# 1_MCU.net
KiCad netlist of a schematic drawn in Altium Designer
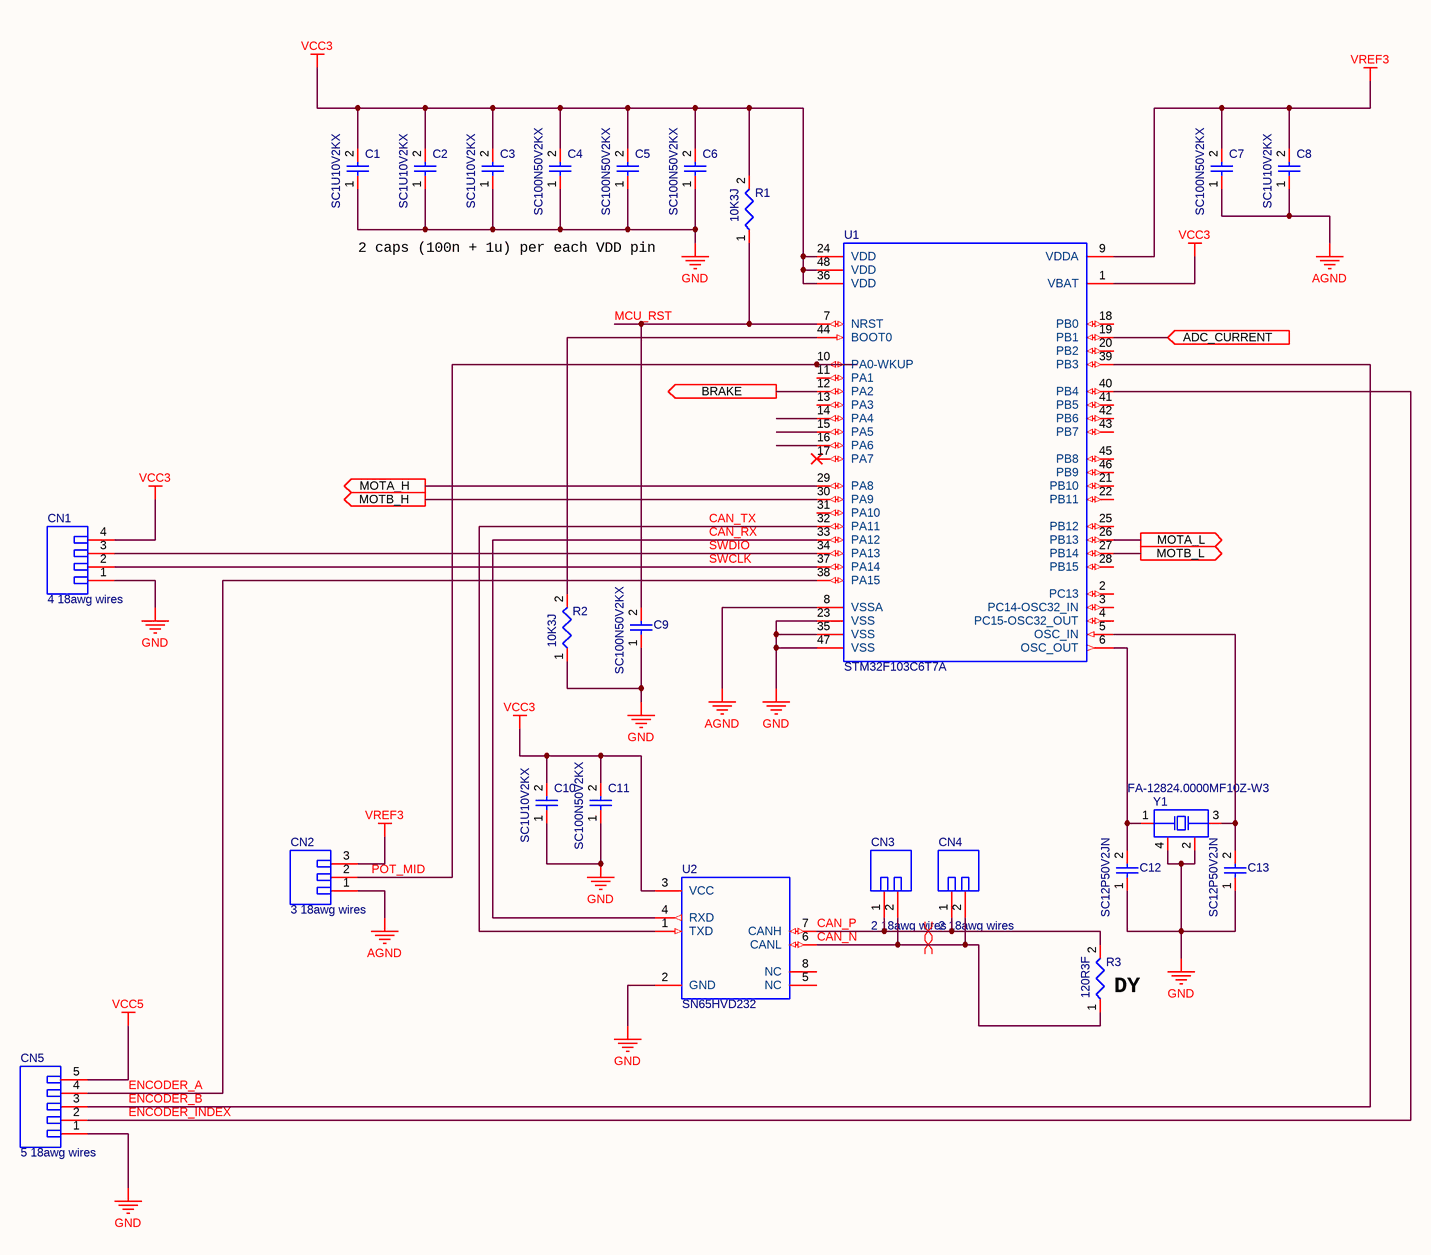
[diagram p0: 1_MCU.SchDoc]

(export (version "E")
  (design (tool "Eeschema 10.0.6"))
  (components
    (comp (ref "C1")
      (value "SC1U10V2KX")
      (footprint "CAPC0402(1005)60_L")
      (description "CAP 1uF 10V ±10% 0402 (1005 Metric) Thickness 0.6mm SMD")
      (libsource (lib "Schlib") (part "CAP(0402)1UF10V"))
    )
    (comp (ref "C2")
      (value "SC1U10V2KX")
      (footprint "CAPC0402(1005)60_L")
      (description "CAP 1uF 10V ±10% 0402 (1005 Metric) Thickness 0.6mm SMD")
      (libsource (lib "Schlib") (part "CAP(0402)1UF10V"))
    )
    (comp (ref "C3")
      (value "SC1U10V2KX")
      (footprint "CAPC0402(1005)60_L")
      (description "CAP 1uF 10V ±10% 0402 (1005 Metric) Thickness 0.6mm SMD")
      (libsource (lib "Schlib") (part "CAP(0402)1UF10V"))
    )
    (comp (ref "C4")
      (value "SC100N50V2KX")
      (footprint "CAPC0402(1005)60_L")
      (description "CAP 100nF 50V ±10% 0402 (1005 Metric) Thickness 0.6mm SMD")
      (libsource (lib "Schlib") (part "CAP(0402)100nF50V"))
    )
    (comp (ref "C5")
      (value "SC100N50V2KX")
      (footprint "CAPC0402(1005)60_L")
      (description "CAP 100nF 50V ±10% 0402 (1005 Metric) Thickness 0.6mm SMD")
      (libsource (lib "Schlib") (part "CAP(0402)100nF50V"))
    )
    (comp (ref "C6")
      (value "SC100N50V2KX")
      (footprint "CAPC0402(1005)60_L")
      (description "CAP 100nF 50V ±10% 0402 (1005 Metric) Thickness 0.6mm SMD")
      (libsource (lib "Schlib") (part "CAP(0402)100nF50V"))
    )
    (comp (ref "C7")
      (value "SC100N50V2KX")
      (footprint "CAPC0402(1005)60_L")
      (description "CAP 100nF 50V ±10% 0402 (1005 Metric) Thickness 0.6mm SMD")
      (libsource (lib "Schlib") (part "CAP(0402)100nF50V"))
    )
    (comp (ref "C8")
      (value "SC1U10V2KX")
      (footprint "CAPC0402(1005)60_L")
      (description "CAP 1uF 10V ±10% 0402 (1005 Metric) Thickness 0.6mm SMD")
      (libsource (lib "Schlib") (part "CAP(0402)1UF10V"))
    )
    (comp (ref "C9")
      (value "SC100N50V2KX")
      (footprint "CAPC0402(1005)60_L")
      (description "CAP 100nF 50V ±10% 0402 (1005 Metric) Thickness 0.6mm SMD")
      (libsource (lib "Schlib") (part "CAP(0402)100nF50V"))
    )
    (comp (ref "C10")
      (value "SC1U10V2KX")
      (footprint "CAPC0402(1005)60_L")
      (description "CAP 1uF 10V ±10% 0402 (1005 Metric) Thickness 0.6mm SMD")
      (libsource (lib "Schlib") (part "CAP(0402)1UF10V"))
    )
    (comp (ref "C11")
      (value "SC100N50V2KX")
      (footprint "CAPC0402(1005)60_L")
      (description "CAP 100nF 50V ±10% 0402 (1005 Metric) Thickness 0.6mm SMD")
      (libsource (lib "Schlib") (part "CAP(0402)100nF50V"))
    )
    (comp (ref "C12")
      (value "SC12P50V2JN")
      (footprint "CAPC0402(1005)33_L")
      (description "CAP 12pF 50V ±5% 0402 (1005 Metric) Thickness 0.33mm SMD")
      (libsource (lib "PUMAlib") (part "CAP12pF"))
    )
    (comp (ref "C13")
      (value "SC12P50V2JN")
      (footprint "CAPC0402(1005)33_L")
      (description "CAP 12pF 50V ±5% 0402 (1005 Metric) Thickness 0.33mm SMD")
      (libsource (lib "PUMAlib") (part "CAP12pF"))
    )
    (comp (ref "CN1")
      (value "4 18awg wires")
      (footprint "4PHEADERS-2D54")
      (description "4 holes for 18awg wire")
      (fields (field (name "MANUFACTURER") "JST"))
      (libsource (lib "PUMAlib") (part "4PIN-CN"))
    )
    (comp (ref "CN2")
      (value "3 18awg wires")
      (footprint "3PHEADERS-2D54")
      (description "3 holes for 18awg wire")
      (fields (field (name "MANUFACTURER") "JST"))
      (libsource (lib "PUMAlib") (part "3PIN-CN"))
    )
    (comp (ref "CN3")
      (value "2 18awg wires")
      (footprint "2PHEADERS-2D54")
      (description "2 holes for 18awg wire")
      (fields (field (name "MANUFACTURER") "JST"))
      (libsource (lib "PDB") (part "2PIN-CN"))
    )
    (comp (ref "CN4")
      (value "2 18awg wires")
      (footprint "2PHEADERS-2D54")
      (description "2 holes for 18awg wire")
      (fields (field (name "MANUFACTURER") "JST"))
      (libsource (lib "PDB") (part "2PIN-CN"))
    )
    (comp (ref "CN5")
      (value "5 18awg wires")
      (footprint "5PHEADERS-2D54")
      (description "5 holes for 18awg wire")
      (fields (field (name "MANUFACTURER") "JST"))
      (libsource (lib "PUMAlib") (part "5PIN-CN"))
    )
    (comp (ref "R1")
      (value "10K3J")
      (footprint "RESC0603(1608)_L")
      (description "10K 0.1W 5% 0603 (1608 Metric)  SMD")
      (libsource (lib "Schlib") (part "RES0(0603)_10K"))
    )
    (comp (ref "R2")
      (value "10K3J")
      (footprint "RESC0603(1608)_L")
      (description "10K 0.1W 5% 0603 (1608 Metric)  SMD")
      (libsource (lib "Schlib") (part "RES0(0603)_10K"))
    )
    (comp (ref "R3")
      (value "120R3F")
      (footprint "RESC0603(1608)_L")
      (description "100R 0.1W 1% 0603 (1608 Metric)  SMD")
      (libsource (lib "PUMAlib") (part "RES0(0603)_120R"))
    )
    (comp (ref "U1")
      (value "STM32F103C6T7A")
      (footprint "TSQFP50P900X900X160-48L")
      (description "ARM® Cortex®-M3 STM32F1 Microcontroller IC 32-Bit 72MHz 32KB 48-LFQP (7x7)")
      (libsource (lib "PUMAlib") (part "STM32F103C6T7A"))
    )
    (comp (ref "U2")
      (value "SN65HVD232")
      (footprint "SOIC127P600X175-8L")
      (description "IC CAN TRANSCEIVER 8-SOIC")
      (libsource (lib "PUMAlib") (part "CAN_SN65HVD232D"))
    )
    (comp (ref "Y1")
      (value "FA-12824.0000MF10Z-W3")
      (footprint "QRTZ-12mhz")
      (description "Crystal, 24 MHz, +/- 10 ppm, -20 to 75 degC, 4-Pin SMD, RoHS, Tape and Reel")
      (fields (field (name "TOLERANCE") "10ppm"))
      (libsource (lib "PUMAlib") (part "XTAL-1-3-4"))
    )
  )
  (nets
    (net (code "1") (name "/ADC_CURRENT") (class "Default")
      (node (ref "U1") (pin "19") (pinfunction "PB1_19") (pintype "bidirectional"))
    )
    (net (code "2") (name "/BRAKE") (class "Default")
      (node (ref "U1") (pin "12") (pinfunction "PA2_12") (pintype "bidirectional"))
    )
    (net (code "3") (name "/CAN_N") (class "Default")
      (node (ref "CN3") (pin "2") (pinfunction "2_2") (pintype "passive"))
      (node (ref "CN4") (pin "2") (pinfunction "2_2") (pintype "passive"))
      (node (ref "R3") (pin "1") (pinfunction "1_1") (pintype "passive"))
      (node (ref "U2") (pin "6") (pinfunction "CANL_6") (pintype "bidirectional"))
    )
    (net (code "4") (name "/CAN_P") (class "Default")
      (node (ref "CN3") (pin "1") (pinfunction "1_1") (pintype "passive"))
      (node (ref "CN4") (pin "1") (pinfunction "1_1") (pintype "passive"))
      (node (ref "R3") (pin "2") (pinfunction "2_2") (pintype "passive"))
      (node (ref "U2") (pin "7") (pinfunction "CANH_7") (pintype "bidirectional"))
    )
    (net (code "5") (name "/CAN_RX") (class "Default")
      (node (ref "U1") (pin "33") (pinfunction "PA12_33") (pintype "bidirectional"))
      (node (ref "U2") (pin "4") (pinfunction "RXD_4") (pintype "output"))
    )
    (net (code "6") (name "/CAN_TX") (class "Default")
      (node (ref "U1") (pin "32") (pinfunction "PA11_32") (pintype "bidirectional"))
      (node (ref "U2") (pin "1") (pinfunction "TXD_1") (pintype "input"))
    )
    (net (code "7") (name "/ENCODER_A") (class "Default")
      (node (ref "CN5") (pin "4") (pinfunction "4_4") (pintype "passive"))
      (node (ref "U1") (pin "38") (pinfunction "PA15_38") (pintype "bidirectional"))
    )
    (net (code "8") (name "/ENCODER_B") (class "Default")
      (node (ref "CN5") (pin "3") (pinfunction "3_3") (pintype "passive"))
      (node (ref "U1") (pin "39") (pinfunction "PB3_39") (pintype "bidirectional"))
    )
    (net (code "9") (name "/ENCODER_INDEX") (class "Default")
      (node (ref "CN5") (pin "2") (pinfunction "2_2") (pintype "passive"))
      (node (ref "U1") (pin "40") (pinfunction "PB4_40") (pintype "bidirectional"))
    )
    (net (code "10") (name "/MCU_RST") (class "Default")
      (node (ref "C9") (pin "2") (pinfunction "2_2") (pintype "passive"))
      (node (ref "R1") (pin "1") (pinfunction "1_1") (pintype "passive"))
      (node (ref "U1") (pin "7") (pinfunction "NRST_7") (pintype "bidirectional"))
    )
    (net (code "11") (name "/MOTA_H") (class "Default")
      (node (ref "U1") (pin "29") (pinfunction "PA8_29") (pintype "bidirectional"))
    )
    (net (code "12") (name "/MOTA_L") (class "Default")
      (node (ref "U1") (pin "26") (pinfunction "PB13_26") (pintype "bidirectional"))
    )
    (net (code "13") (name "/MOTB_H") (class "Default")
      (node (ref "U1") (pin "30") (pinfunction "PA9_30") (pintype "bidirectional"))
    )
    (net (code "14") (name "/MOTB_L") (class "Default")
      (node (ref "U1") (pin "27") (pinfunction "PB14_27") (pintype "bidirectional"))
    )
    (net (code "15") (name "/POT_MID") (class "Default")
      (node (ref "CN2") (pin "2") (pinfunction "2_2") (pintype "passive"))
      (node (ref "U1") (pin "10") (pinfunction "PA0-WKUP_10") (pintype "bidirectional"))
    )
    (net (code "16") (name "/SWCLK") (class "Default")
      (node (ref "CN1") (pin "2") (pinfunction "2_2") (pintype "passive"))
      (node (ref "U1") (pin "37") (pinfunction "PA14_37") (pintype "bidirectional"))
    )
    (net (code "17") (name "/SWDIO") (class "Default")
      (node (ref "CN1") (pin "3") (pinfunction "3_3") (pintype "passive"))
      (node (ref "U1") (pin "34") (pinfunction "PA13_34") (pintype "bidirectional"))
    )
    (net (code "18") (name "AGND") (class "Default")
      (node (ref "C7") (pin "1") (pinfunction "1_1") (pintype "passive"))
      (node (ref "C8") (pin "1") (pinfunction "1_1") (pintype "passive"))
      (node (ref "CN2") (pin "1") (pinfunction "1_1") (pintype "passive"))
      (node (ref "U1") (pin "8") (pinfunction "VSSA_8") (pintype "power_in"))
    )
    (net (code "19") (name "GND") (class "Default")
      (node (ref "C1") (pin "1") (pinfunction "1_1") (pintype "passive"))
      (node (ref "C10") (pin "1") (pinfunction "1_1") (pintype "passive"))
      (node (ref "C11") (pin "1") (pinfunction "1_1") (pintype "passive"))
      (node (ref "C12") (pin "1") (pinfunction "1_1") (pintype "passive"))
      (node (ref "C13") (pin "1") (pinfunction "1_1") (pintype "passive"))
      (node (ref "C2") (pin "1") (pinfunction "1_1") (pintype "passive"))
      (node (ref "C3") (pin "1") (pinfunction "1_1") (pintype "passive"))
      (node (ref "C4") (pin "1") (pinfunction "1_1") (pintype "passive"))
      (node (ref "C5") (pin "1") (pinfunction "1_1") (pintype "passive"))
      (node (ref "C6") (pin "1") (pinfunction "1_1") (pintype "passive"))
      (node (ref "C9") (pin "1") (pinfunction "1_1") (pintype "passive"))
      (node (ref "CN1") (pin "1") (pinfunction "1_1") (pintype "passive"))
      (node (ref "CN5") (pin "1") (pinfunction "1_1") (pintype "passive"))
      (node (ref "R2") (pin "1") (pinfunction "1_1") (pintype "passive"))
      (node (ref "U1") (pin "23") (pinfunction "VSS_23") (pintype "power_in"))
      (node (ref "U1") (pin "35") (pinfunction "VSS_35") (pintype "power_in"))
      (node (ref "U1") (pin "47") (pinfunction "VSS_47") (pintype "power_in"))
      (node (ref "U2") (pin "2") (pinfunction "GND_2") (pintype "power_in"))
      (node (ref "Y1") (pin "2") (pinfunction "NC_2") (pintype "power_in"))
      (node (ref "Y1") (pin "4") (pinfunction "NC_4") (pintype "power_in"))
    )
    (net (code "20") (name "Net-(U1-BOOT0)") (class "Default")
      (node (ref "R2") (pin "2") (pinfunction "2_2") (pintype "passive"))
      (node (ref "U1") (pin "44") (pinfunction "BOOT0_44") (pintype "input"))
    )
    (net (code "21") (name "Net-(U1-OSC_IN)") (class "Default")
      (node (ref "C13") (pin "2") (pinfunction "2_2") (pintype "passive"))
      (node (ref "U1") (pin "5") (pinfunction "OSC_IN_5") (pintype "input"))
      (node (ref "Y1") (pin "3") (pinfunction "X2_3") (pintype "passive"))
    )
    (net (code "22") (name "Net-(U1-OSC_OUT)") (class "Default")
      (node (ref "C12") (pin "2") (pinfunction "2_2") (pintype "passive"))
      (node (ref "U1") (pin "6") (pinfunction "OSC_OUT_6") (pintype "output"))
      (node (ref "Y1") (pin "1") (pinfunction "X1_1") (pintype "passive"))
    )
    (net (code "23") (name "VCC3") (class "Default")
      (node (ref "C1") (pin "2") (pinfunction "2_2") (pintype "passive"))
      (node (ref "C10") (pin "2") (pinfunction "2_2") (pintype "passive"))
      (node (ref "C11") (pin "2") (pinfunction "2_2") (pintype "passive"))
      (node (ref "C2") (pin "2") (pinfunction "2_2") (pintype "passive"))
      (node (ref "C3") (pin "2") (pinfunction "2_2") (pintype "passive"))
      (node (ref "C4") (pin "2") (pinfunction "2_2") (pintype "passive"))
      (node (ref "C5") (pin "2") (pinfunction "2_2") (pintype "passive"))
      (node (ref "C6") (pin "2") (pinfunction "2_2") (pintype "passive"))
      (node (ref "CN1") (pin "4") (pinfunction "4_4") (pintype "passive"))
      (node (ref "R1") (pin "2") (pinfunction "2_2") (pintype "passive"))
      (node (ref "U1") (pin "1") (pinfunction "VBAT_1") (pintype "power_in"))
      (node (ref "U1") (pin "24") (pinfunction "VDD_24") (pintype "power_in"))
      (node (ref "U1") (pin "36") (pinfunction "VDD_36") (pintype "power_in"))
      (node (ref "U1") (pin "48") (pinfunction "VDD_48") (pintype "power_in"))
      (node (ref "U2") (pin "3") (pinfunction "VCC_3") (pintype "power_in"))
    )
    (net (code "24") (name "VCC5") (class "Default")
      (node (ref "CN5") (pin "5") (pinfunction "5_5") (pintype "passive"))
    )
    (net (code "25") (name "VREF3") (class "Default")
      (node (ref "C7") (pin "2") (pinfunction "2_2") (pintype "passive"))
      (node (ref "C8") (pin "2") (pinfunction "2_2") (pintype "passive"))
      (node (ref "CN2") (pin "3") (pinfunction "3_3") (pintype "passive"))
      (node (ref "U1") (pin "9") (pinfunction "VDDA_9") (pintype "power_in"))
    )
    (net (code "26") (name "unconnected-(U1-PA1-Pad11)") (class "Default")
      (node (ref "U1") (pin "11") (pinfunction "PA1_11") (pintype "bidirectional"))
    )
    (net (code "27") (name "unconnected-(U1-PA3-Pad13)") (class "Default")
      (node (ref "U1") (pin "13") (pinfunction "PA3_13") (pintype "bidirectional"))
    )
    (net (code "28") (name "unconnected-(U1-PA4-Pad14)") (class "Default")
      (node (ref "U1") (pin "14") (pinfunction "PA4_14") (pintype "bidirectional"))
    )
    (net (code "29") (name "unconnected-(U1-PA5-Pad15)") (class "Default")
      (node (ref "U1") (pin "15") (pinfunction "PA5_15") (pintype "bidirectional"))
    )
    (net (code "30") (name "unconnected-(U1-PA6-Pad16)") (class "Default")
      (node (ref "U1") (pin "16") (pinfunction "PA6_16") (pintype "bidirectional"))
    )
    (net (code "31") (name "unconnected-(U1-PA7-Pad17)") (class "Default")
      (node (ref "U1") (pin "17") (pinfunction "PA7_17") (pintype "bidirectional+no_connect"))
    )
    (net (code "32") (name "unconnected-(U1-PA10-Pad31)") (class "Default")
      (node (ref "U1") (pin "31") (pinfunction "PA10_31") (pintype "bidirectional"))
    )
    (net (code "33") (name "unconnected-(U1-PB0-Pad18)") (class "Default")
      (node (ref "U1") (pin "18") (pinfunction "PB0_18") (pintype "bidirectional"))
    )
    (net (code "34") (name "unconnected-(U1-PB2-Pad20)") (class "Default")
      (node (ref "U1") (pin "20") (pinfunction "PB2_20") (pintype "bidirectional"))
    )
    (net (code "35") (name "unconnected-(U1-PB5-Pad41)") (class "Default")
      (node (ref "U1") (pin "41") (pinfunction "PB5_41") (pintype "bidirectional"))
    )
    (net (code "36") (name "unconnected-(U1-PB6-Pad42)") (class "Default")
      (node (ref "U1") (pin "42") (pinfunction "PB6_42") (pintype "bidirectional"))
    )
    (net (code "37") (name "unconnected-(U1-PB7-Pad43)") (class "Default")
      (node (ref "U1") (pin "43") (pinfunction "PB7_43") (pintype "bidirectional"))
    )
    (net (code "38") (name "unconnected-(U1-PB8-Pad45)") (class "Default")
      (node (ref "U1") (pin "45") (pinfunction "PB8_45") (pintype "bidirectional"))
    )
    (net (code "39") (name "unconnected-(U1-PB9-Pad46)") (class "Default")
      (node (ref "U1") (pin "46") (pinfunction "PB9_46") (pintype "bidirectional"))
    )
    (net (code "40") (name "unconnected-(U1-PB10-Pad21)") (class "Default")
      (node (ref "U1") (pin "21") (pinfunction "PB10_21") (pintype "bidirectional"))
    )
    (net (code "41") (name "unconnected-(U1-PB11-Pad22)") (class "Default")
      (node (ref "U1") (pin "22") (pinfunction "PB11_22") (pintype "bidirectional"))
    )
    (net (code "42") (name "unconnected-(U1-PB12-Pad25)") (class "Default")
      (node (ref "U1") (pin "25") (pinfunction "PB12_25") (pintype "bidirectional"))
    )
    (net (code "43") (name "unconnected-(U1-PB15-Pad28)") (class "Default")
      (node (ref "U1") (pin "28") (pinfunction "PB15_28") (pintype "bidirectional"))
    )
    (net (code "44") (name "unconnected-(U1-PC13-Pad2)") (class "Default")
      (node (ref "U1") (pin "2") (pinfunction "PC13_2") (pintype "bidirectional"))
    )
    (net (code "45") (name "unconnected-(U1-PC14-OSC32_IN-Pad3)") (class "Default")
      (node (ref "U1") (pin "3") (pinfunction "PC14-OSC32_IN_3") (pintype "bidirectional"))
    )
    (net (code "46") (name "unconnected-(U1-PC15-OSC32_OUT-Pad4)") (class "Default")
      (node (ref "U1") (pin "4") (pinfunction "PC15-OSC32_OUT_4") (pintype "bidirectional"))
    )
    (net (code "47") (name "unconnected-(U2-NC-Pad5)") (class "Default")
      (node (ref "U2") (pin "5") (pinfunction "NC_5") (pintype "passive"))
    )
    (net (code "48") (name "unconnected-(U2-NC-Pad8)") (class "Default")
      (node (ref "U2") (pin "8") (pinfunction "NC_8") (pintype "passive"))
    )
  )
)
